# Current_Comparator.net
KiCad netlist of a schematic drawn in Altium Designer
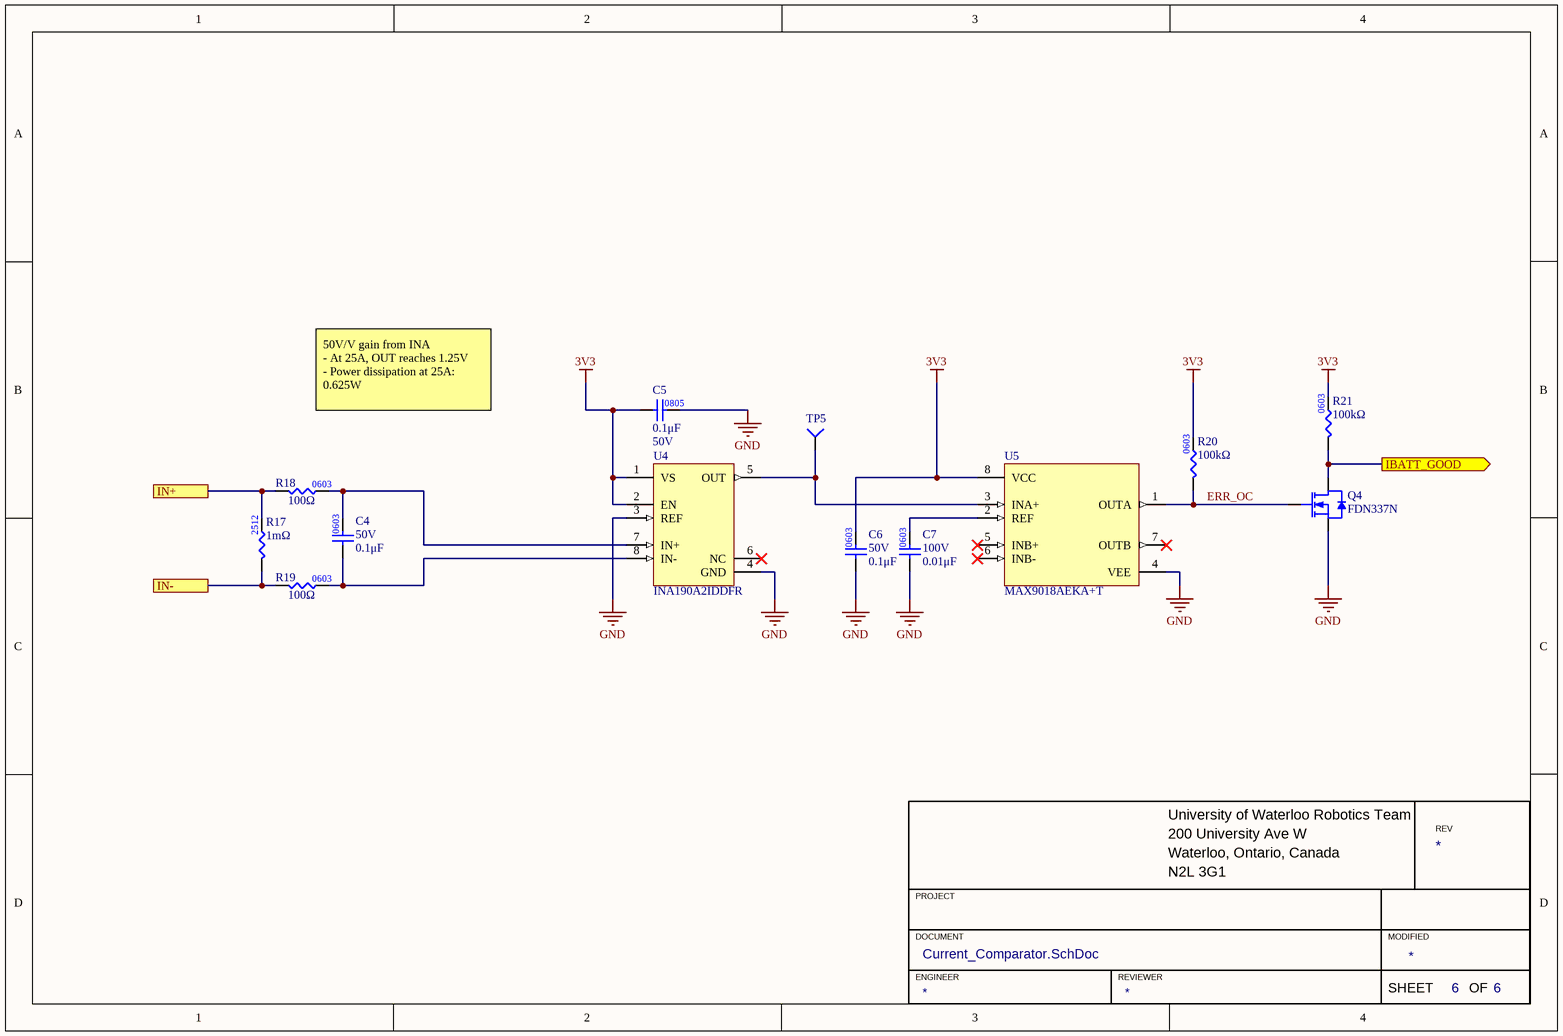
[diagram p0: Current_Comparator.SchDoc]

(export (version "E")
  (design (tool "Eeschema 10.0.6"))
  (components
    (comp (ref "C4")
      (value "0.1μF")
      (footprint "CAP0603")
      (description "CAP CER 0.1UF 50V X7R 0603")
      (fields (field (name "VOLTAGE RATING") "50V") (field (name "Comment") "CAP_0.1uF_50V_0603"))
      (libsource (lib "Personal_Schematic_Library_2022") (part "CAP_0.1uF_50V_0603"))
    )
    (comp (ref "C5")
      (value "0.1μF")
      (footprint "CAP0805")
      (description "CAP CER 0.1UF 50V X7R 0805")
      (fields
        (field (name "VOLTAGE RATING") "50V")
        (field (name "LCSC PART #") "C49678")
        (field (name "Comment") "CAP_0.1uF_50V_0805")
      )
      (libsource (lib "UWRT_Schematic_Library_2020") (part "CAP_0.1uF_50V_0805"))
    )
    (comp (ref "C6")
      (value "0.1μF")
      (footprint "CAP0603")
      (description "CAP CER 0.1UF 50V X7R 0603")
      (fields (field (name "VOLTAGE RATING") "50V") (field (name "Comment") "CAP_0.1uF_50V_0603"))
      (libsource (lib "UWRT_Schematic_Library_2020") (part "CAP_0.1uF_50V_0603"))
    )
    (comp (ref "C7")
      (value "0.01μF")
      (footprint "CAP0603")
      (description "CAP CER 0.01uF 100V X7R 0603")
      (fields (field (name "VOLTAGE RATING") "100V") (field (name "Comment") "CAP_0.01uF_100V_0603"))
      (libsource (lib "Personal_Schematic_Library_2022") (part "CAP_0.01uF_100V_0603"))
    )
    (comp (ref "Q4")
      (value "NMOS_30V_2.2A")
      (footprint "NMOS_SSOT-3")
      (description "MOSFET N-CH 30V 2.2A SUPERSOT3")
      (fields (field (name "MANUFACTURER PART NUMBER 1") "FDN337N"))
      (libsource (lib "Personal_Schematic_Library_2022") (part "NMOS_30V_2.2A"))
    )
    (comp (ref "R17")
      (value "1mΩ")
      (footprint "RESC6532X75N")
      (description "RES 1 mOHM 1% 3W 2512")
      (fields (field (name "Comment") "RES_1mΩ_2512_1%"))
      (libsource (lib "UWRT_Schematic_Library_2020") (part "RES_1mΩ_2512_1%"))
    )
    (comp (ref "R18")
      (value "100Ω")
      (footprint "RES0603")
      (description "RES 100 OHM 1% 1/10W 0603")
      (fields (field (name "Comment") "RES_100Ω_0603_1%"))
      (libsource (lib "Personal_Schematic_Library_2022") (part "RES_100Ω_0603_1%"))
    )
    (comp (ref "R19")
      (value "100Ω")
      (footprint "RES0603")
      (description "RES 100 OHM 1% 1/10W 0603")
      (fields (field (name "Comment") "RES_100Ω_0603_1%"))
      (libsource (lib "Personal_Schematic_Library_2022") (part "RES_100Ω_0603_1%"))
    )
    (comp (ref "R20")
      (value "100kΩ")
      (footprint "RES0603")
      (description "RES 100K OHM 1% 1/10W 0603")
      (fields (field (name "Comment") "RES_100kΩ_0603_1%"))
      (libsource (lib "Personal_Schematic_Library_2022") (part "RES_100kΩ_0603_1%"))
    )
    (comp (ref "R21")
      (value "100kΩ")
      (footprint "RES0603")
      (description "RES 100K OHM 1% 1/10W 0603")
      (fields (field (name "Comment") "RES_100kΩ_0603_1%"))
      (libsource (lib "Personal_Schematic_Library_2022") (part "RES_100kΩ_0603_1%"))
    )
    (comp (ref "TP5")
      (value "TESTPOINT_1MM_CIRCLE")
      (footprint "TESTPOINT_CIRCLE_1MM")
      (description "TESTPOINT 1MM CIRCLE")
      (libsource (lib "UWRT_Schematic_Library_2020") (part "TESTPOINT_1MM_CIRCLE"))
    )
    (comp (ref "U4")
      (value "INA190A2IDDFR")
      (footprint "SOT23-8 TI")
      (description "IC CURR SENSE 1 CIRCUIT SOT23-8")
      (fields (field (name "MANUFACTURER PART NUMBER 1") "INA190A2IDDFR"))
      (libsource (lib "Personal_Schematic_Library_2022") (part "INA190A2IDDFR"))
    )
    (comp (ref "U5")
      (value "IC_COMPARATOR_MAX9018")
      (footprint "SOT23-8 MAXIM")
      (description "IC COMPARATOR DUAL SOT23-8")
      (fields (field (name "MANUFACTURER PART NUMBER 1") "MAX9018AEKA+T"))
      (libsource (lib "Personal_Schematic_Library_2022") (part "IC_COMPARATOR_MAX9018"))
    )
  )
  (nets
    (net (code "1") (name "/ERR_OC") (class "Default")
      (node (ref "Q4") (pin "1") (pinfunction "GATE_1") (pintype "passive"))
      (node (ref "R20") (pin "1") (pinfunction "1_1") (pintype "passive"))
      (node (ref "U5") (pin "1") (pinfunction "OUTA_1") (pintype "output"))
    )
    (net (code "2") (name "/IBATT_GOOD") (class "Default")
      (node (ref "Q4") (pin "3") (pinfunction "DRAIN_3") (pintype "passive"))
      (node (ref "R21") (pin "1") (pinfunction "1_1") (pintype "passive"))
    )
    (net (code "3") (name "/IN+") (class "Default")
      (node (ref "R17") (pin "2") (pinfunction "2_2") (pintype "passive"))
      (node (ref "R18") (pin "1") (pinfunction "1_1") (pintype "passive"))
    )
    (net (code "4") (name "/IN-") (class "Default")
      (node (ref "R17") (pin "1") (pinfunction "1_1") (pintype "passive"))
      (node (ref "R19") (pin "1") (pinfunction "1_1") (pintype "passive"))
    )
    (net (code "5") (name "3V3") (class "Default")
      (node (ref "C5") (pin "1") (pinfunction "1_1") (pintype "passive"))
      (node (ref "C6") (pin "2") (pinfunction "2_2") (pintype "passive"))
      (node (ref "R20") (pin "2") (pinfunction "2_2") (pintype "passive"))
      (node (ref "R21") (pin "2") (pinfunction "2_2") (pintype "passive"))
      (node (ref "U4") (pin "1") (pinfunction "VS_1") (pintype "power_in"))
      (node (ref "U4") (pin "2") (pinfunction "EN_2") (pintype "passive"))
      (node (ref "U5") (pin "8") (pinfunction "VCC_8") (pintype "power_in"))
    )
    (net (code "6") (name "GND") (class "Default")
      (node (ref "C5") (pin "2") (pinfunction "2_2") (pintype "passive"))
      (node (ref "C6") (pin "1") (pinfunction "1_1") (pintype "passive"))
      (node (ref "C7") (pin "1") (pinfunction "1_1") (pintype "passive"))
      (node (ref "Q4") (pin "2") (pinfunction "SOURCE_2") (pintype "passive"))
      (node (ref "U4") (pin "3") (pinfunction "REF_3") (pintype "input"))
      (node (ref "U4") (pin "4") (pinfunction "GND_4") (pintype "passive"))
      (node (ref "U5") (pin "4") (pinfunction "VEE_4") (pintype "power_in"))
    )
    (net (code "7") (name "Net-(TP5-=value)") (class "Default")
      (node (ref "TP5") (pin "1") (pinfunction "=value_1") (pintype "passive"))
      (node (ref "U4") (pin "5") (pinfunction "OUT_5") (pintype "output"))
      (node (ref "U5") (pin "3") (pinfunction "INA+_3") (pintype "input"))
    )
    (net (code "8") (name "Net-(U4-IN+)") (class "Default")
      (node (ref "C4") (pin "2") (pinfunction "2_2") (pintype "passive"))
      (node (ref "R18") (pin "2") (pinfunction "2_2") (pintype "passive"))
      (node (ref "U4") (pin "7") (pinfunction "IN+_7") (pintype "input"))
    )
    (net (code "9") (name "Net-(U4-IN-)") (class "Default")
      (node (ref "C4") (pin "1") (pinfunction "1_1") (pintype "passive"))
      (node (ref "R19") (pin "2") (pinfunction "2_2") (pintype "passive"))
      (node (ref "U4") (pin "8") (pinfunction "IN-_8") (pintype "input"))
    )
    (net (code "10") (name "Net-(U5-REF)") (class "Default")
      (node (ref "C7") (pin "2") (pinfunction "2_2") (pintype "passive"))
      (node (ref "U5") (pin "2") (pinfunction "REF_2") (pintype "input"))
    )
    (net (code "11") (name "unconnected-(U4-NC-Pad6)") (class "Default")
      (node (ref "U4") (pin "6") (pinfunction "NC_6") (pintype "passive+no_connect"))
    )
    (net (code "12") (name "unconnected-(U5-INB+-Pad5)") (class "Default")
      (node (ref "U5") (pin "5") (pinfunction "INB+_5") (pintype "input+no_connect"))
    )
    (net (code "13") (name "unconnected-(U5-INB--Pad6)") (class "Default")
      (node (ref "U5") (pin "6") (pinfunction "INB-_6") (pintype "input+no_connect"))
    )
    (net (code "14") (name "unconnected-(U5-OUTB-Pad7)") (class "Default")
      (node (ref "U5") (pin "7") (pinfunction "OUTB_7") (pintype "output+no_connect"))
    )
  )
)
